# WIFI.net
KiCad netlist of a schematic drawn in Altium Designer
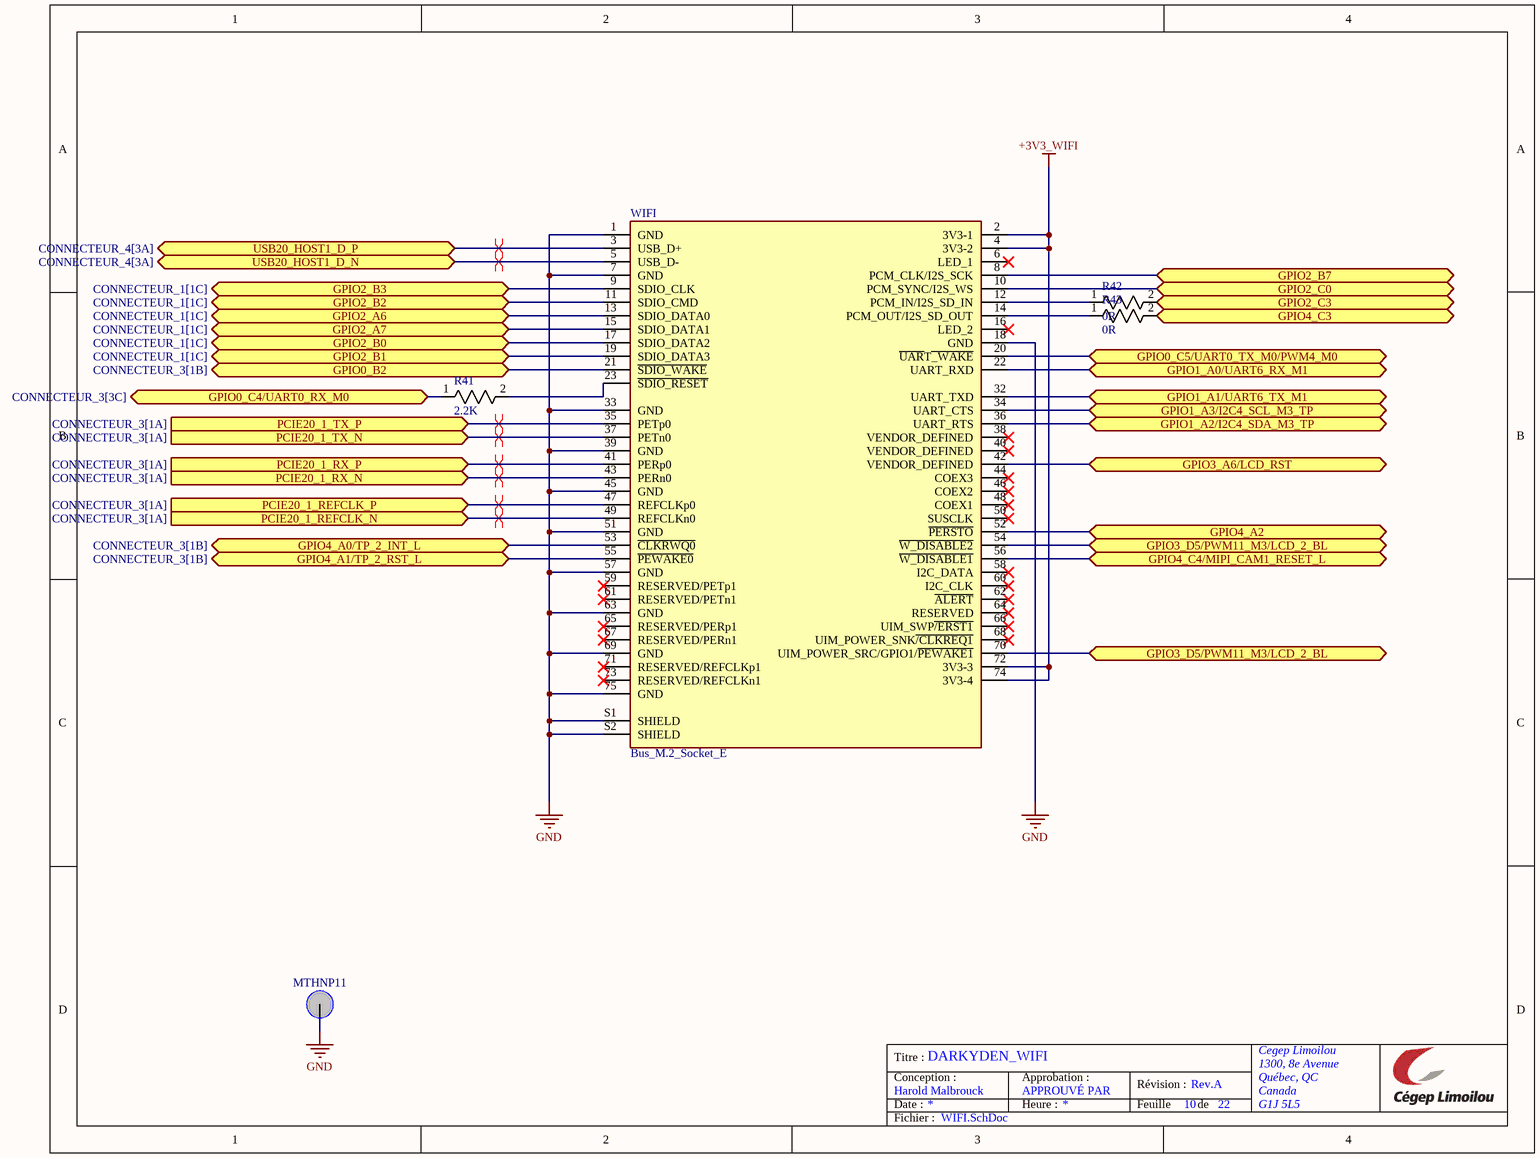
[diagram p0: WIFI.SchDoc]

(export (version "E")
  (design (tool "Eeschema 10.0.6"))
  (components
    (comp (ref "MTHNP11")
      (value "Mounting Hole Non-Plated 3.2mm")
      (footprint "SamacSys:MTHNP3P2MM")
      (description "Mounting Hole Non-Plated 3.2mm drill hole")
      (libsource (lib "DARKYDEN") (part "MTHNP3P2MM"))
    )
    (comp (ref "R41")
      (value "2.2K")
      (footprint "SamacSys:RESC1608X55N")
      (description "2.2 kOhm, ï¿½ 5%, 100 mW, 0603 [1608 Metric], Thick Film, General Purpose")
      (fields
        (field (name "MANUFACTURER_PART_NUMBER") "ERJ-3GEYJ222V")
        (field (name "MOUSER PART NUMBER") "667-ERJ-3GEYJ222V")
      )
      (libsource (lib "DARKYDEN") (part "ERJ-3GEYJ222V"))
    )
    (comp (ref "R42")
      (value "0R")
      (footprint "SamacSys:RESC1608X55N")
      (description "Zero Ohm Resistor, Jumper, 0603 [1608 Metric], Thick Film, 100 mW, 1 A, Surface Mount")
      (fields
        (field (name "MANUFACTURER_PART_NUMBER") "ERJ-3GEY0R00V")
        (field (name "MOUSER PART NUMBER") "667-ERJ-3GEY0R00V")
      )
      (libsource (lib "DARKYDEN") (part "ERJ-3GEY0R00V"))
    )
    (comp (ref "R43")
      (value "0R")
      (footprint "SamacSys:RESC1608X55N")
      (description "Zero Ohm Resistor, Jumper, 0603 [1608 Metric], Thick Film, 100 mW, 1 A, Surface Mount")
      (fields
        (field (name "MANUFACTURER_PART_NUMBER") "ERJ-3GEY0R00V")
        (field (name "MOUSER PART NUMBER") "667-ERJ-3GEY0R00V")
      )
      (libsource (lib "DARKYDEN") (part "ERJ-3GEY0R00V"))
    )
    (comp (ref "WIFI")
      (value "Bus_M.2_Socket_E")
      (footprint "AMPHENOL_MDT320E01001")
      (description "PCIe M.2 Connectors, Storage and Server Connector, P=0.5mm, H=3.2mm, Key E,30Î¼in Au Plating")
      (fields (field (name "MP") "MDT320E01001") (field (name "MF") "Amphenol ICC"))
      (libsource (lib "Bus_M.2_Socket_E") (part "Bus_M.2_Socket_E"))
    )
  )
  (nets
    (net (code "1") (name "+3V3_WIFI") (class "Default")
      (node (ref "WIFI") (pin "2") (pinfunction "3V3-1_2") (pintype "power_in"))
      (node (ref "WIFI") (pin "4") (pinfunction "3V3-2_4") (pintype "power_in"))
      (node (ref "WIFI") (pin "72") (pinfunction "3V3-3_72") (pintype "power_in"))
      (node (ref "WIFI") (pin "74") (pinfunction "3V3-4_74") (pintype "power_in"))
    )
    (net (code "2") (name "/GPIO0_B2") (class "Default")
      (node (ref "WIFI") (pin "21") (pinfunction "~{SDIO_WAKE}_21") (pintype "passive"))
    )
    (net (code "3") (name "/GPIO0_C4{slash}UART0_RX_M0") (class "Default")
      (node (ref "R41") (pin "1") (pinfunction "1_1") (pintype "passive"))
    )
    (net (code "4") (name "/GPIO0_C5{slash}UART0_TX_M0{slash}PWM4_M0") (class "Default")
      (node (ref "WIFI") (pin "20") (pinfunction "~{UAR}T~{_WAKE}_20") (pintype "passive"))
    )
    (net (code "5") (name "/GPIO1_A0{slash}UART6_RX_M1") (class "Default")
      (node (ref "WIFI") (pin "22") (pinfunction "UART_RXD_22") (pintype "passive"))
    )
    (net (code "6") (name "/GPIO1_A1{slash}UART6_TX_M1") (class "Default")
      (node (ref "WIFI") (pin "32") (pinfunction "UART_TXD_32") (pintype "passive"))
    )
    (net (code "7") (name "/GPIO1_A2{slash}I2C4_SDA_M3_TP") (class "Default")
      (node (ref "WIFI") (pin "36") (pinfunction "UART_RTS_36") (pintype "passive"))
    )
    (net (code "8") (name "/GPIO1_A3{slash}I2C4_SCL_M3_TP") (class "Default")
      (node (ref "WIFI") (pin "34") (pinfunction "UART_CTS_34") (pintype "passive"))
    )
    (net (code "9") (name "/GPIO2_A6") (class "Default")
      (node (ref "WIFI") (pin "13") (pinfunction "SDIO_DATA0_13") (pintype "passive"))
    )
    (net (code "10") (name "/GPIO2_A7") (class "Default")
      (node (ref "WIFI") (pin "15") (pinfunction "SDIO_DATA1_15") (pintype "passive"))
    )
    (net (code "11") (name "/GPIO2_B0") (class "Default")
      (node (ref "WIFI") (pin "17") (pinfunction "SDIO_DATA2_17") (pintype "passive"))
    )
    (net (code "12") (name "/GPIO2_B1") (class "Default")
      (node (ref "WIFI") (pin "19") (pinfunction "SDIO_DATA3_19") (pintype "passive"))
    )
    (net (code "13") (name "/GPIO2_B2") (class "Default")
      (node (ref "WIFI") (pin "11") (pinfunction "SDIO_CMD_11") (pintype "passive"))
    )
    (net (code "14") (name "/GPIO2_B3") (class "Default")
      (node (ref "WIFI") (pin "9") (pinfunction "SDIO_CLK_9") (pintype "passive"))
    )
    (net (code "15") (name "/GPIO2_B7") (class "Default")
      (node (ref "WIFI") (pin "8") (pinfunction "PCM_CLK/I2S_SCK_8") (pintype "passive"))
    )
    (net (code "16") (name "/GPIO2_C0") (class "Default")
      (node (ref "WIFI") (pin "10") (pinfunction "PCM_SYNC/I2S_WS_10") (pintype "passive"))
    )
    (net (code "17") (name "/GPIO2_C3") (class "Default")
      (node (ref "R42") (pin "2") (pinfunction "2_2") (pintype "passive"))
    )
    (net (code "18") (name "/GPIO3_A6{slash}LCD_RST") (class "Default")
      (node (ref "WIFI") (pin "42") (pinfunction "VENDOR_DEFINED_42") (pintype "passive"))
    )
    (net (code "19") (name "/GPIO3_D5{slash}PWM11_M3{slash}LCD_2_BL") (class "Default")
      (node (ref "WIFI") (pin "54") (pinfunction "~{W_DISABLE2}_54") (pintype "passive"))
      (node (ref "WIFI") (pin "70") (pinfunction "UIM_POWER_SRC/GPIO1/~{PEWAKE1}_70") (pintype "passive"))
    )
    (net (code "20") (name "/GPIO4_A0{slash}TP_2_INT_L") (class "Default")
      (node (ref "WIFI") (pin "53") (pinfunction "~{CLKRWQ0}_53") (pintype "passive"))
    )
    (net (code "21") (name "/GPIO4_A1{slash}TP_2_RST_L") (class "Default")
      (node (ref "WIFI") (pin "55") (pinfunction "~{PEWAKE0}_55") (pintype "passive"))
    )
    (net (code "22") (name "/GPIO4_A2") (class "Default")
      (node (ref "WIFI") (pin "52") (pinfunction "~{PERSTO}_52") (pintype "passive"))
    )
    (net (code "23") (name "/GPIO4_C3") (class "Default")
      (node (ref "R43") (pin "2") (pinfunction "2_2") (pintype "passive"))
    )
    (net (code "24") (name "/GPIO4_C4{slash}MIPI_CAM1_RESET_L") (class "Default")
      (node (ref "WIFI") (pin "56") (pinfunction "~{W_DISABLE1}_56") (pintype "passive"))
    )
    (net (code "25") (name "/PCIE20_1_REFCLK_N") (class "Default")
      (node (ref "WIFI") (pin "49") (pinfunction "REFCLKn0_49") (pintype "passive"))
    )
    (net (code "26") (name "/PCIE20_1_REFCLK_P") (class "Default")
      (node (ref "WIFI") (pin "47") (pinfunction "REFCLKp0_47") (pintype "passive"))
    )
    (net (code "27") (name "/PCIE20_1_RX_N") (class "Default")
      (node (ref "WIFI") (pin "43") (pinfunction "PERn0_43") (pintype "passive"))
    )
    (net (code "28") (name "/PCIE20_1_RX_P") (class "Default")
      (node (ref "WIFI") (pin "41") (pinfunction "PERp0_41") (pintype "passive"))
    )
    (net (code "29") (name "/PCIE20_1_TX_N") (class "Default")
      (node (ref "WIFI") (pin "37") (pinfunction "PETn0_37") (pintype "passive"))
    )
    (net (code "30") (name "/PCIE20_1_TX_P") (class "Default")
      (node (ref "WIFI") (pin "35") (pinfunction "PETp0_35") (pintype "passive"))
    )
    (net (code "31") (name "/USB20_HOST1_D_N") (class "Default")
      (node (ref "WIFI") (pin "5") (pinfunction "USB_D-_5") (pintype "passive"))
    )
    (net (code "32") (name "/USB20_HOST1_D_P") (class "Default")
      (node (ref "WIFI") (pin "3") (pinfunction "USB_D+_3") (pintype "passive"))
    )
    (net (code "33") (name "GND") (class "Default")
      (node (ref "MTHNP11") (pin "1") (pinfunction "1_1") (pintype "passive"))
      (node (ref "WIFI") (pin "1") (pinfunction "GND_1") (pintype "passive"))
      (node (ref "WIFI") (pin "18") (pinfunction "GND_18") (pintype "passive"))
      (node (ref "WIFI") (pin "33") (pinfunction "GND_33") (pintype "passive"))
      (node (ref "WIFI") (pin "39") (pinfunction "GND_39") (pintype "passive"))
      (node (ref "WIFI") (pin "45") (pinfunction "GND_45") (pintype "passive"))
      (node (ref "WIFI") (pin "51") (pinfunction "GND_51") (pintype "passive"))
      (node (ref "WIFI") (pin "57") (pinfunction "GND_57") (pintype "passive"))
      (node (ref "WIFI") (pin "63") (pinfunction "GND_63") (pintype "passive"))
      (node (ref "WIFI") (pin "69") (pinfunction "GND_69") (pintype "passive"))
      (node (ref "WIFI") (pin "7") (pinfunction "GND_7") (pintype "passive"))
      (node (ref "WIFI") (pin "75") (pinfunction "GND_75") (pintype "passive"))
      (node (ref "WIFI") (pin "S1") (pinfunction "SHIELD_S1") (pintype "passive"))
      (node (ref "WIFI") (pin "S2") (pinfunction "SHIELD_S2") (pintype "passive"))
    )
    (net (code "34") (name "Net-(WIFI-PCM_IN{slash}I2S_SD_IN)") (class "Default")
      (node (ref "R42") (pin "1") (pinfunction "1_1") (pintype "passive"))
      (node (ref "WIFI") (pin "12") (pinfunction "PCM_IN/I2S_SD_IN_12") (pintype "passive"))
    )
    (net (code "35") (name "Net-(WIFI-PCM_OUT{slash}I2S_SD_OUT)") (class "Default")
      (node (ref "R43") (pin "1") (pinfunction "1_1") (pintype "passive"))
      (node (ref "WIFI") (pin "14") (pinfunction "PCM_OUT/I2S_SD_OUT_14") (pintype "passive"))
    )
    (net (code "36") (name "Net-(WIFI-~{SDIO_RESET})") (class "Default")
      (node (ref "R41") (pin "2") (pinfunction "2_2") (pintype "passive"))
      (node (ref "WIFI") (pin "23") (pinfunction "~{SDIO_RESET}_23") (pintype "passive"))
    )
    (net (code "37") (name "unconnected-(WIFI-COEX1-Pad48)") (class "Default")
      (node (ref "WIFI") (pin "48") (pinfunction "COEX1_48") (pintype "passive+no_connect"))
    )
    (net (code "38") (name "unconnected-(WIFI-COEX2-Pad46)") (class "Default")
      (node (ref "WIFI") (pin "46") (pinfunction "COEX2_46") (pintype "passive+no_connect"))
    )
    (net (code "39") (name "unconnected-(WIFI-COEX3-Pad44)") (class "Default")
      (node (ref "WIFI") (pin "44") (pinfunction "COEX3_44") (pintype "passive+no_connect"))
    )
    (net (code "40") (name "unconnected-(WIFI-I2C_CLK-Pad60)") (class "Default")
      (node (ref "WIFI") (pin "60") (pinfunction "I2C_CLK_60") (pintype "passive+no_connect"))
    )
    (net (code "41") (name "unconnected-(WIFI-I2C_DATA-Pad58)") (class "Default")
      (node (ref "WIFI") (pin "58") (pinfunction "I2C_DATA_58") (pintype "passive+no_connect"))
    )
    (net (code "42") (name "unconnected-(WIFI-LED_1-Pad6)") (class "Default")
      (node (ref "WIFI") (pin "6") (pinfunction "LED_1_6") (pintype "passive+no_connect"))
    )
    (net (code "43") (name "unconnected-(WIFI-LED_2-Pad16)") (class "Default")
      (node (ref "WIFI") (pin "16") (pinfunction "LED_2_16") (pintype "passive+no_connect"))
    )
    (net (code "44") (name "unconnected-(WIFI-RESERVED-Pad64)") (class "Default")
      (node (ref "WIFI") (pin "64") (pinfunction "RESERVED_64") (pintype "passive+no_connect"))
    )
    (net (code "45") (name "unconnected-(WIFI-RESERVED{slash}PERn1-Pad67)") (class "Default")
      (node (ref "WIFI") (pin "67") (pinfunction "RESERVED/PERn1_67") (pintype "passive+no_connect"))
    )
    (net (code "46") (name "unconnected-(WIFI-RESERVED{slash}PERp1-Pad65)") (class "Default")
      (node (ref "WIFI") (pin "65") (pinfunction "RESERVED/PERp1_65") (pintype "passive+no_connect"))
    )
    (net (code "47") (name "unconnected-(WIFI-RESERVED{slash}PETn1-Pad61)") (class "Default")
      (node (ref "WIFI") (pin "61") (pinfunction "RESERVED/PETn1_61") (pintype "passive+no_connect"))
    )
    (net (code "48") (name "unconnected-(WIFI-RESERVED{slash}PETp1-Pad59)") (class "Default")
      (node (ref "WIFI") (pin "59") (pinfunction "RESERVED/PETp1_59") (pintype "passive+no_connect"))
    )
    (net (code "49") (name "unconnected-(WIFI-RESERVED{slash}REFCLKn1-Pad73)") (class "Default")
      (node (ref "WIFI") (pin "73") (pinfunction "RESERVED/REFCLKn1_73") (pintype "passive+no_connect"))
    )
    (net (code "50") (name "unconnected-(WIFI-RESERVED{slash}REFCLKp1-Pad71)") (class "Default")
      (node (ref "WIFI") (pin "71") (pinfunction "RESERVED/REFCLKp1_71") (pintype "passive+no_connect"))
    )
    (net (code "51") (name "unconnected-(WIFI-SUSCLK-Pad50)") (class "Default")
      (node (ref "WIFI") (pin "50") (pinfunction "SUSCLK_50") (pintype "passive+no_connect"))
    )
    (net (code "52") (name "unconnected-(WIFI-UIM_POWER_SNK~{{slash}CLKREQ1}-Pad68)") (class "Default")
      (node (ref "WIFI") (pin "68") (pinfunction "UIM_POWER_SNK~{/CLKREQ1}_68") (pintype "passive+no_connect"))
    )
    (net (code "53") (name "unconnected-(WIFI-UIM_SWP~{{slash}ERST1}-Pad66)") (class "Default")
      (node (ref "WIFI") (pin "66") (pinfunction "UIM_SWP~{/ERST1}_66") (pintype "passive+no_connect"))
    )
    (net (code "54") (name "unconnected-(WIFI-VENDOR_DEFINED-Pad38)") (class "Default")
      (node (ref "WIFI") (pin "38") (pinfunction "VENDOR_DEFINED_38") (pintype "passive+no_connect"))
    )
    (net (code "55") (name "unconnected-(WIFI-VENDOR_DEFINED-Pad40)") (class "Default")
      (node (ref "WIFI") (pin "40") (pinfunction "VENDOR_DEFINED_40") (pintype "passive+no_connect"))
    )
    (net (code "56") (name "unconnected-(WIFI-~{ALERT}-Pad62)") (class "Default")
      (node (ref "WIFI") (pin "62") (pinfunction "~{ALERT}_62") (pintype "passive+no_connect"))
    )
  )
)
